# SCH_AOG_Test_Board_2023-11-17.net
KiCad netlist of a schematic drawn in EasyEDA
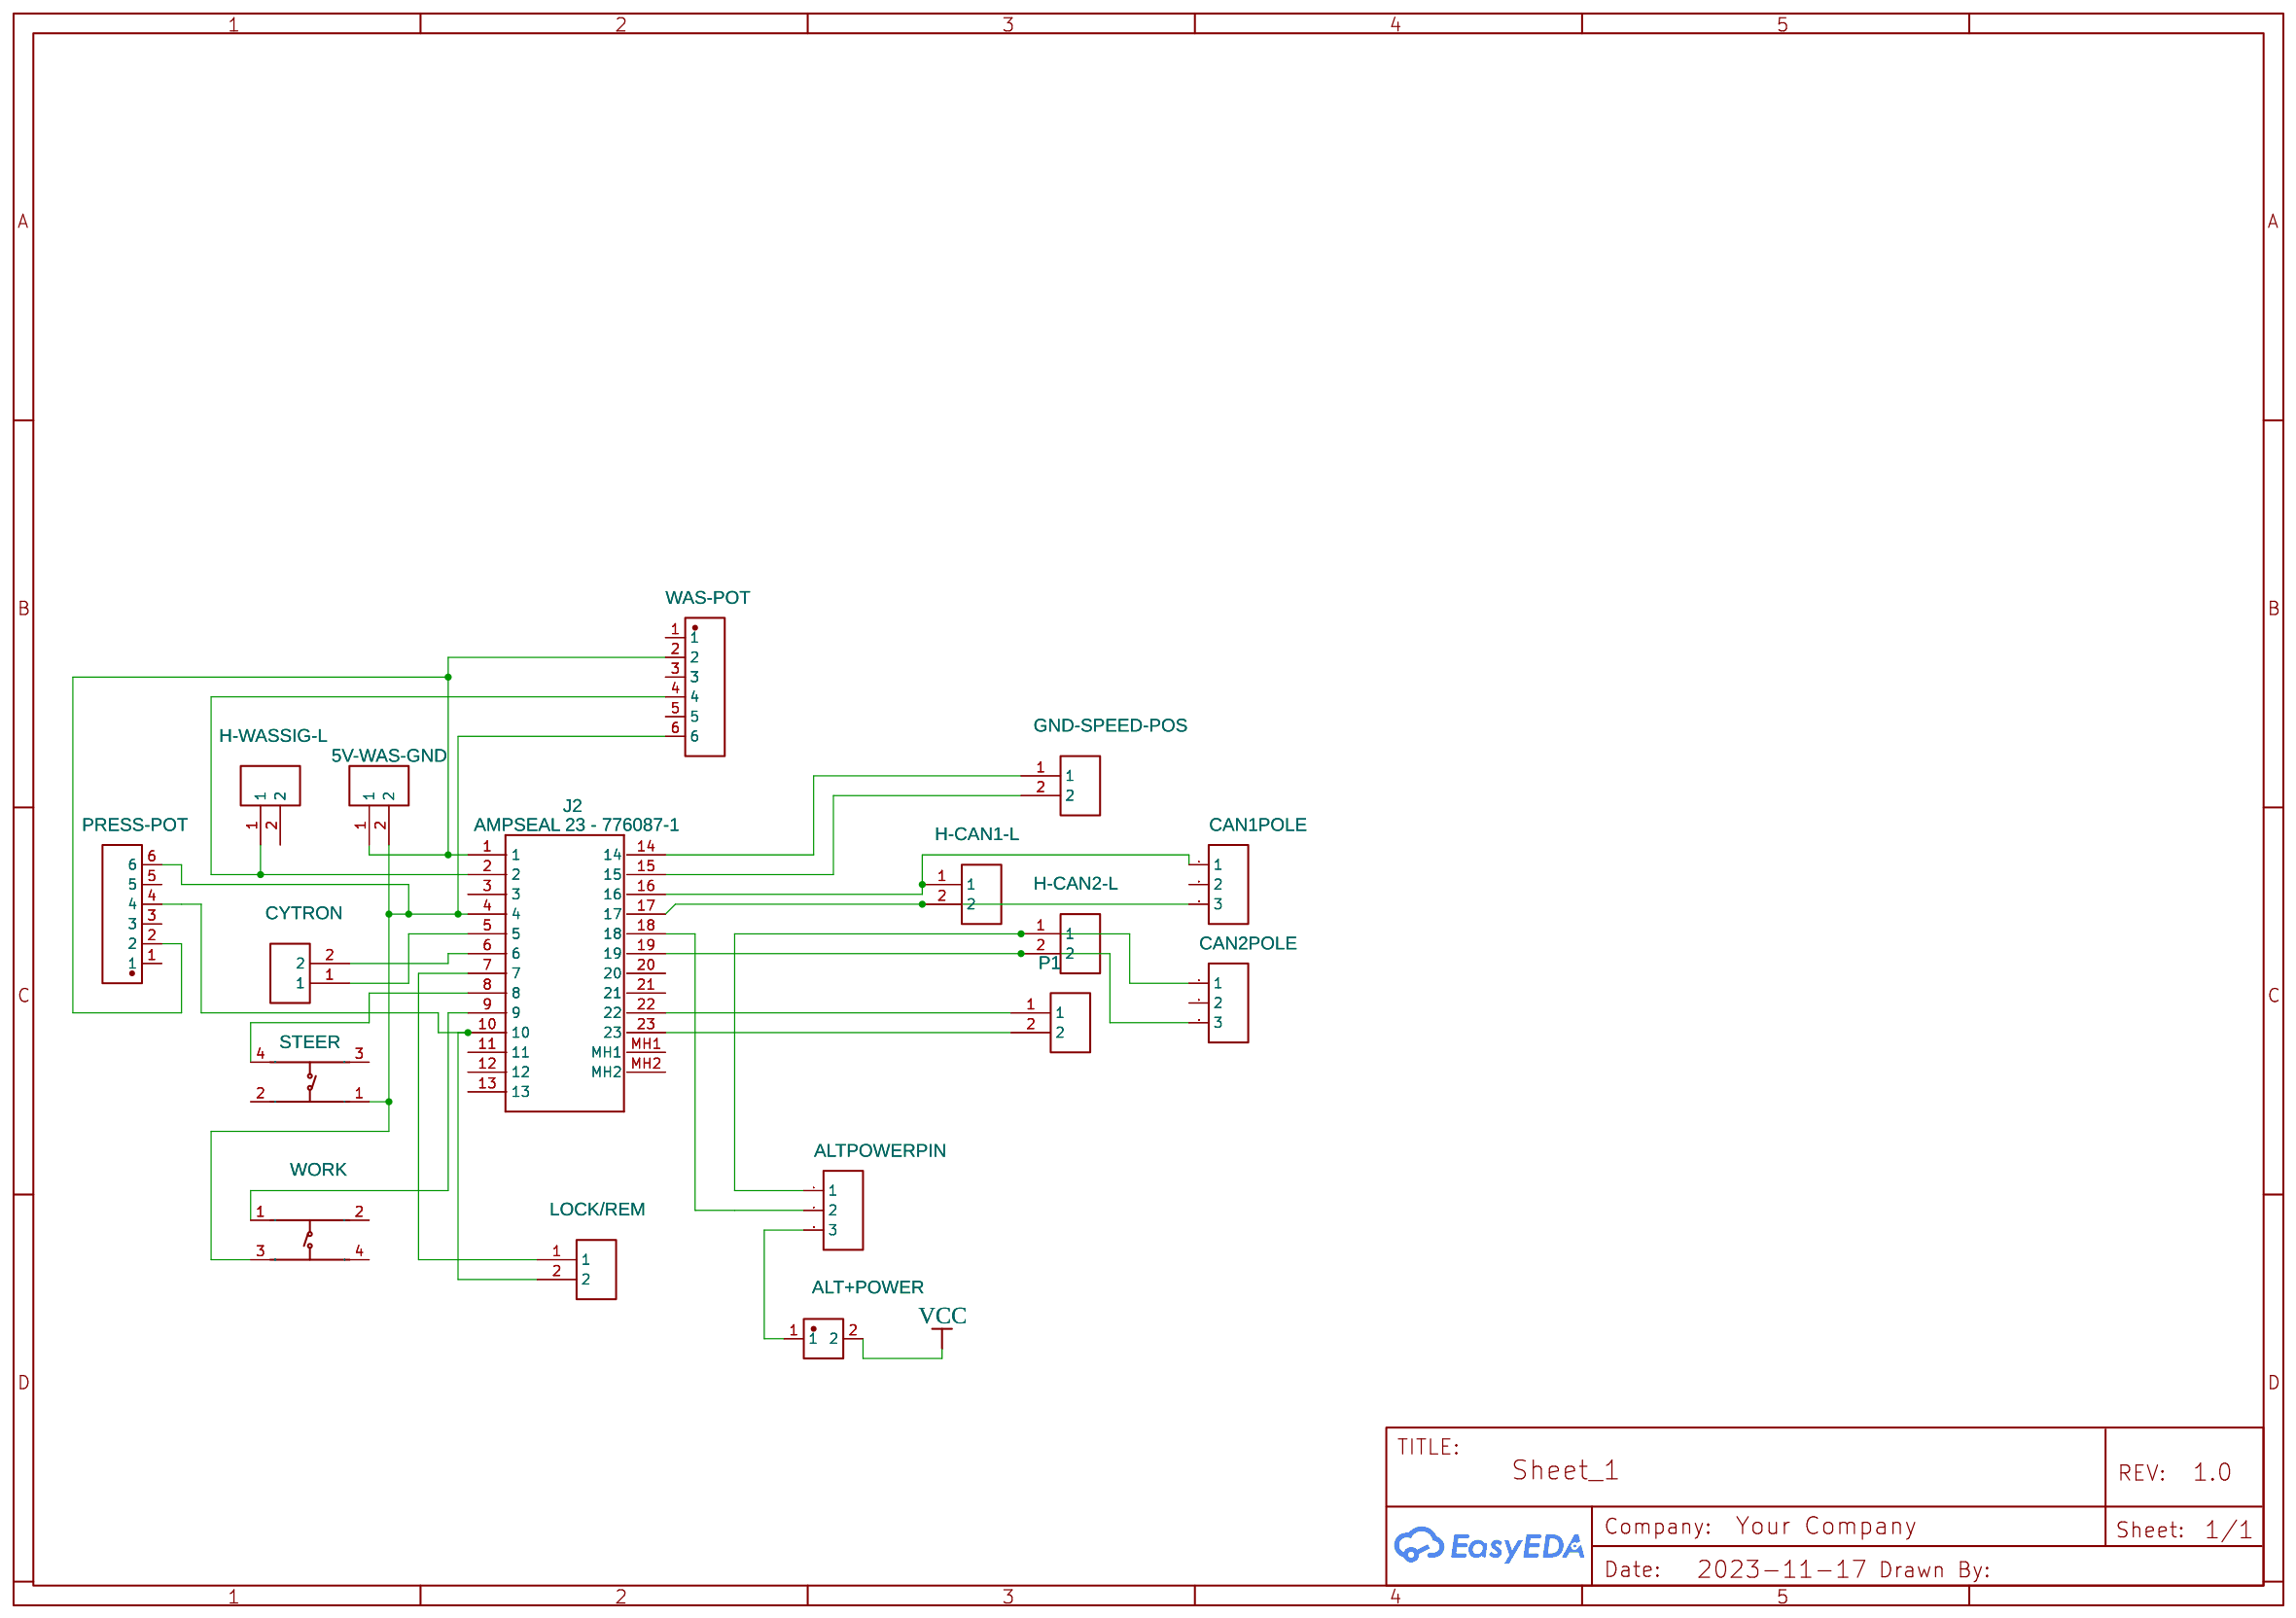
[diagram p0: schematic sheet]

(export (version "E")
  (design (tool "Eeschema 10.0.6"))
  (components
    (comp (ref "5V-WAS-GND")
      (value "WJ500V-5.08-2P-14-00A")
      (fields
        (field (name "Manufacturer Part") "WJ500V-5.08-2P")
        (field (name "Manufacturer") "KANGNEX(康奈克斯电气)")
      )
      (libsource (lib "") (part "WJ500V-5.08-2P-14-00A_2"))
    )
    (comp (ref "ALT+POWER")
      (value "EST026")
      (fields (field (name "Manufacturer") "xcfuse(旭程)"))
      (libsource (lib "") (part "EST026"))
    )
    (comp (ref "ALTPOWERPIN")
      (value "Header-Male-2.54_1x3")
      (fields (field (name "Manufacturer Part") "2.54-1*3P针") (field (name "Manufacturer") "BOOMELE(博穆精密)"))
      (libsource (lib "") (part "Header-Male-2.54_1x3_1"))
    )
    (comp (ref "CAN1POLE")
      (value "Header-Male-2.54_1x3")
      (fields (field (name "Manufacturer Part") "2.54-1*3P针") (field (name "Manufacturer") "BOOMELE(博穆精密)"))
      (libsource (lib "") (part "Header-Male-2.54_1x3_2"))
    )
    (comp (ref "CAN2POLE")
      (value "Header-Male-2.54_1x3")
      (fields (field (name "Manufacturer Part") "2.54-1*3P针") (field (name "Manufacturer") "BOOMELE(博穆精密)"))
      (libsource (lib "") (part "Header-Male-2.54_1x3"))
    )
    (comp (ref "CYTRON")
      (value "WJ500V-5.08-2P-14-00A")
      (fields
        (field (name "Manufacturer Part") "WJ500V-5.08-2P")
        (field (name "Manufacturer") "KANGNEX(康奈克斯电气)")
      )
      (libsource (lib "") (part "WJ500V-5.08-2P-14-00A_4"))
    )
    (comp (ref "GND-SPEED-POS")
      (value "WJ500V-5.08-2P-14-00A")
      (fields
        (field (name "Manufacturer Part") "WJ500V-5.08-2P")
        (field (name "Manufacturer") "KANGNEX(康奈克斯电气)")
      )
      (libsource (lib "") (part "WJ500V-5.08-2P-14-00A_3"))
    )
    (comp (ref "H-CAN1-L")
      (value "WJ500V-5.08-2P-14-00A")
      (fields
        (field (name "Manufacturer Part") "WJ500V-5.08-2P")
        (field (name "Manufacturer") "KANGNEX(康奈克斯电气)")
      )
      (libsource (lib "") (part "WJ500V-5.08-2P-14-00A_1"))
    )
    (comp (ref "H-CAN2-L")
      (value "WJ500V-5.08-2P-14-00A")
      (fields
        (field (name "Manufacturer Part") "WJ500V-5.08-2P")
        (field (name "Manufacturer") "KANGNEX(康奈克斯电气)")
      )
      (libsource (lib "") (part "WJ500V-5.08-2P-14-00A_7"))
    )
    (comp (ref "H-WASSIG-L")
      (value "WJ500V-5.08-2P-14-00A")
      (fields
        (field (name "Manufacturer Part") "WJ500V-5.08-2P")
        (field (name "Manufacturer") "KANGNEX(康奈克斯电气)")
      )
      (libsource (lib "") (part "WJ500V-5.08-2P-14-00A"))
    )
    (comp (ref "J2") (value "AMPSEAL 23 - 776087-1") (libsource (lib "") (part "AMPSEAL 23 - 776087-1")))
    (comp (ref "LOCK/REM")
      (value "WJ500V-5.08-2P-14-00A")
      (fields
        (field (name "Manufacturer Part") "WJ500V-5.08-2P")
        (field (name "Manufacturer") "KANGNEX(康奈克斯电气)")
      )
      (libsource (lib "") (part "WJ500V-5.08-2P-14-00A_6"))
    )
    (comp (ref "P1")
      (value "WJ500V-5.08-2P-14-00A")
      (fields
        (field (name "Manufacturer Part") "WJ500V-5.08-2P")
        (field (name "Manufacturer") "KANGNEX(康奈克斯电气)")
      )
      (libsource (lib "") (part "WJ500V-5.08-2P-14-00A_5"))
    )
    (comp (ref "PRESS-POT")
      (value "Header-Female-2.54_1x6")
      (fields (field (name "Manufacturer Part") "2.54-1*6P母") (field (name "Manufacturer") "BOOMELE(博穆精密)"))
      (libsource (lib "") (part "Header-Female-2.54_1x6_1"))
    )
    (comp (ref "STEER")
      (value "TS665CJ")
      (fields (field (name "Manufacturer") "SHOU HAN(首韩)"))
      (libsource (lib "") (part "TS665CJ_1"))
    )
    (comp (ref "WAS-POT")
      (value "Header-Female-2.54_1x6")
      (fields (field (name "Manufacturer Part") "2.54-1*6P母") (field (name "Manufacturer") "BOOMELE(博穆精密)"))
      (libsource (lib "") (part "Header-Female-2.54_1x6"))
    )
    (comp (ref "WORK")
      (value "TS665CJ")
      (fields (field (name "Manufacturer") "SHOU HAN(首韩)"))
      (libsource (lib "") (part "TS665CJ"))
    )
  )
  (nets
    (net (code "1") (name "Net-(5V-WAS-GND-Pad1)") (class "Default")
      (node (ref "5V-WAS-GND") (pin "1") (pinfunction "1_1") (pintype "unspecified"))
      (node (ref "J2") (pin "1") (pinfunction "1_1") (pintype "bidirectional"))
      (node (ref "PRESS-POT") (pin "2") (pinfunction "2_2") (pintype "unspecified"))
      (node (ref "WAS-POT") (pin "2") (pinfunction "2_2") (pintype "unspecified"))
    )
    (net (code "2") (name "Net-(ALT+POWER-Pad1)") (class "Default")
      (node (ref "ALT+POWER") (pin "1") (pinfunction "1_1") (pintype "unspecified"))
      (node (ref "ALTPOWERPIN") (pin "3") (pinfunction "3_3") (pintype "input"))
    )
    (net (code "3") (name "Net-(ALTPOWERPIN-Pad1)") (class "Default")
      (node (ref "ALTPOWERPIN") (pin "1") (pinfunction "1_1") (pintype "input"))
      (node (ref "CAN2POLE") (pin "1") (pinfunction "1_1") (pintype "input"))
      (node (ref "H-CAN2-L") (pin "1") (pinfunction "1_1") (pintype "unspecified"))
    )
    (net (code "4") (name "Net-(ALTPOWERPIN-Pad2)") (class "Default")
      (node (ref "ALTPOWERPIN") (pin "2") (pinfunction "2_2") (pintype "input"))
      (node (ref "J2") (pin "18") (pinfunction "18_18") (pintype "bidirectional"))
    )
    (net (code "5") (name "Net-(CAN1POLE-Pad1)") (class "Default")
      (node (ref "CAN1POLE") (pin "1") (pinfunction "1_1") (pintype "input"))
      (node (ref "H-CAN1-L") (pin "1") (pinfunction "1_1") (pintype "unspecified"))
      (node (ref "J2") (pin "16") (pinfunction "16_16") (pintype "bidirectional"))
    )
    (net (code "6") (name "Net-(CAN1POLE-Pad3)") (class "Default")
      (node (ref "CAN1POLE") (pin "3") (pinfunction "3_3") (pintype "input"))
      (node (ref "H-CAN1-L") (pin "2") (pinfunction "2_2") (pintype "unspecified"))
      (node (ref "J2") (pin "17") (pinfunction "17_17") (pintype "bidirectional"))
    )
    (net (code "7") (name "Net-(CAN2POLE-Pad3)") (class "Default")
      (node (ref "CAN2POLE") (pin "3") (pinfunction "3_3") (pintype "input"))
      (node (ref "H-CAN2-L") (pin "2") (pinfunction "2_2") (pintype "unspecified"))
      (node (ref "J2") (pin "19") (pinfunction "19_19") (pintype "bidirectional"))
    )
    (net (code "8") (name "Net-(CYTRON-Pad1)") (class "Default")
      (node (ref "CYTRON") (pin "1") (pinfunction "1_1") (pintype "unspecified"))
      (node (ref "J2") (pin "5") (pinfunction "5_5") (pintype "bidirectional"))
    )
    (net (code "9") (name "Net-(CYTRON-Pad2)") (class "Default")
      (node (ref "CYTRON") (pin "2") (pinfunction "2_2") (pintype "unspecified"))
      (node (ref "J2") (pin "6") (pinfunction "6_6") (pintype "bidirectional"))
    )
    (net (code "10") (name "Net-(GND-SPEED-POS-Pad1)") (class "Default")
      (node (ref "GND-SPEED-POS") (pin "1") (pinfunction "1_1") (pintype "unspecified"))
      (node (ref "J2") (pin "14") (pinfunction "14_14") (pintype "bidirectional"))
    )
    (net (code "11") (name "Net-(GND-SPEED-POS-Pad2)") (class "Default")
      (node (ref "GND-SPEED-POS") (pin "2") (pinfunction "2_2") (pintype "unspecified"))
      (node (ref "J2") (pin "15") (pinfunction "15_15") (pintype "bidirectional"))
    )
    (net (code "12") (name "Net-(H-WASSIG-L-Pad1)") (class "Default")
      (node (ref "H-WASSIG-L") (pin "1") (pinfunction "1_1") (pintype "unspecified"))
      (node (ref "J2") (pin "2") (pinfunction "2_2") (pintype "bidirectional"))
      (node (ref "WAS-POT") (pin "4") (pinfunction "4_4") (pintype "unspecified"))
    )
    (net (code "13") (name "Net-(J2-Pad7)") (class "Default")
      (node (ref "J2") (pin "7") (pinfunction "7_7") (pintype "bidirectional"))
      (node (ref "LOCK/REM") (pin "1") (pinfunction "1_1") (pintype "unspecified"))
    )
    (net (code "14") (name "Net-(J2-Pad10)") (class "Default")
      (node (ref "J2") (pin "10") (pinfunction "10_10") (pintype "bidirectional"))
      (node (ref "LOCK/REM") (pin "2") (pinfunction "2_2") (pintype "unspecified"))
      (node (ref "PRESS-POT") (pin "4") (pinfunction "4_4") (pintype "unspecified"))
    )
    (net (code "15") (name "Net-(J2-Pad22)") (class "Default")
      (node (ref "J2") (pin "22") (pinfunction "22_22") (pintype "bidirectional"))
      (node (ref "P1") (pin "1") (pinfunction "1_1") (pintype "unspecified"))
    )
    (net (code "16") (name "Net-(J2-Pad23)") (class "Default")
      (node (ref "J2") (pin "23") (pinfunction "23_23") (pintype "bidirectional"))
      (node (ref "P1") (pin "2") (pinfunction "2_2") (pintype "unspecified"))
    )
    (net (code "17") (name "Net-(STEER-A)") (class "Default")
      (node (ref "5V-WAS-GND") (pin "2") (pinfunction "2_2") (pintype "unspecified"))
      (node (ref "J2") (pin "4") (pinfunction "4_4") (pintype "bidirectional"))
      (node (ref "PRESS-POT") (pin "6") (pinfunction "6_6") (pintype "unspecified"))
      (node (ref "STEER") (pin "1") (pinfunction "A_1") (pintype "unspecified"))
      (node (ref "WAS-POT") (pin "6") (pinfunction "6_6") (pintype "unspecified"))
      (node (ref "WORK") (pin "3") (pinfunction "C_3") (pintype "unspecified"))
    )
    (net (code "18") (name "Net-(STEER-D)") (class "Default")
      (node (ref "J2") (pin "8") (pinfunction "8_8") (pintype "bidirectional"))
      (node (ref "STEER") (pin "4") (pinfunction "D_4") (pintype "unspecified"))
    )
    (net (code "19") (name "Net-(WORK-A)") (class "Default")
      (node (ref "J2") (pin "9") (pinfunction "9_9") (pintype "bidirectional"))
      (node (ref "WORK") (pin "1") (pinfunction "A_1") (pintype "unspecified"))
    )
    (net (code "20") (name "VCC") (class "Default")
      (node (ref "ALT+POWER") (pin "2") (pinfunction "2_2") (pintype "unspecified"))
    )
    (net (code "21") (name "unconnected-(CAN1POLE-Pad2)") (class "Default")
      (node (ref "CAN1POLE") (pin "2") (pinfunction "2_2") (pintype "input"))
    )
    (net (code "22") (name "unconnected-(CAN2POLE-Pad2)") (class "Default")
      (node (ref "CAN2POLE") (pin "2") (pinfunction "2_2") (pintype "input"))
    )
    (net (code "23") (name "unconnected-(H-WASSIG-L-Pad2)") (class "Default")
      (node (ref "H-WASSIG-L") (pin "2") (pinfunction "2_2") (pintype "unspecified"))
    )
    (net (code "24") (name "unconnected-(J2-Pad3)") (class "Default")
      (node (ref "J2") (pin "3") (pinfunction "3_3") (pintype "bidirectional"))
    )
    (net (code "25") (name "unconnected-(J2-Pad11)") (class "Default")
      (node (ref "J2") (pin "11") (pinfunction "11_11") (pintype "bidirectional"))
    )
    (net (code "26") (name "unconnected-(J2-Pad12)") (class "Default")
      (node (ref "J2") (pin "12") (pinfunction "12_12") (pintype "bidirectional"))
    )
    (net (code "27") (name "unconnected-(J2-Pad13)") (class "Default")
      (node (ref "J2") (pin "13") (pinfunction "13_13") (pintype "bidirectional"))
    )
    (net (code "28") (name "unconnected-(J2-Pad20)") (class "Default")
      (node (ref "J2") (pin "20") (pinfunction "20_20") (pintype "bidirectional"))
    )
    (net (code "29") (name "unconnected-(J2-Pad21)") (class "Default")
      (node (ref "J2") (pin "21") (pinfunction "21_21") (pintype "bidirectional"))
    )
    (net (code "30") (name "unconnected-(J2-PadMH1)") (class "Default")
      (node (ref "J2") (pin "MH1") (pinfunction "MH1_MH1") (pintype "bidirectional"))
    )
    (net (code "31") (name "unconnected-(J2-PadMH2)") (class "Default")
      (node (ref "J2") (pin "MH2") (pinfunction "MH2_MH2") (pintype "bidirectional"))
    )
    (net (code "32") (name "unconnected-(PRESS-POT-Pad1)") (class "Default")
      (node (ref "PRESS-POT") (pin "1") (pinfunction "1_1") (pintype "unspecified"))
    )
    (net (code "33") (name "unconnected-(PRESS-POT-Pad3)") (class "Default")
      (node (ref "PRESS-POT") (pin "3") (pinfunction "3_3") (pintype "unspecified"))
    )
    (net (code "34") (name "unconnected-(PRESS-POT-Pad5)") (class "Default")
      (node (ref "PRESS-POT") (pin "5") (pinfunction "5_5") (pintype "unspecified"))
    )
    (net (code "35") (name "unconnected-(STEER-B-Pad2)") (class "Default")
      (node (ref "STEER") (pin "2") (pinfunction "B_2") (pintype "unspecified"))
    )
    (net (code "36") (name "unconnected-(STEER-C-Pad3)") (class "Default")
      (node (ref "STEER") (pin "3") (pinfunction "C_3") (pintype "unspecified"))
    )
    (net (code "37") (name "unconnected-(WAS-POT-Pad1)") (class "Default")
      (node (ref "WAS-POT") (pin "1") (pinfunction "1_1") (pintype "unspecified"))
    )
    (net (code "38") (name "unconnected-(WAS-POT-Pad3)") (class "Default")
      (node (ref "WAS-POT") (pin "3") (pinfunction "3_3") (pintype "unspecified"))
    )
    (net (code "39") (name "unconnected-(WAS-POT-Pad5)") (class "Default")
      (node (ref "WAS-POT") (pin "5") (pinfunction "5_5") (pintype "unspecified"))
    )
    (net (code "40") (name "unconnected-(WORK-B-Pad2)") (class "Default")
      (node (ref "WORK") (pin "2") (pinfunction "B_2") (pintype "unspecified"))
    )
    (net (code "41") (name "unconnected-(WORK-D-Pad4)") (class "Default")
      (node (ref "WORK") (pin "4") (pinfunction "D_4") (pintype "unspecified"))
    )
  )
)
